# main.net
KiCad netlist of a schematic drawn in Altium Designer
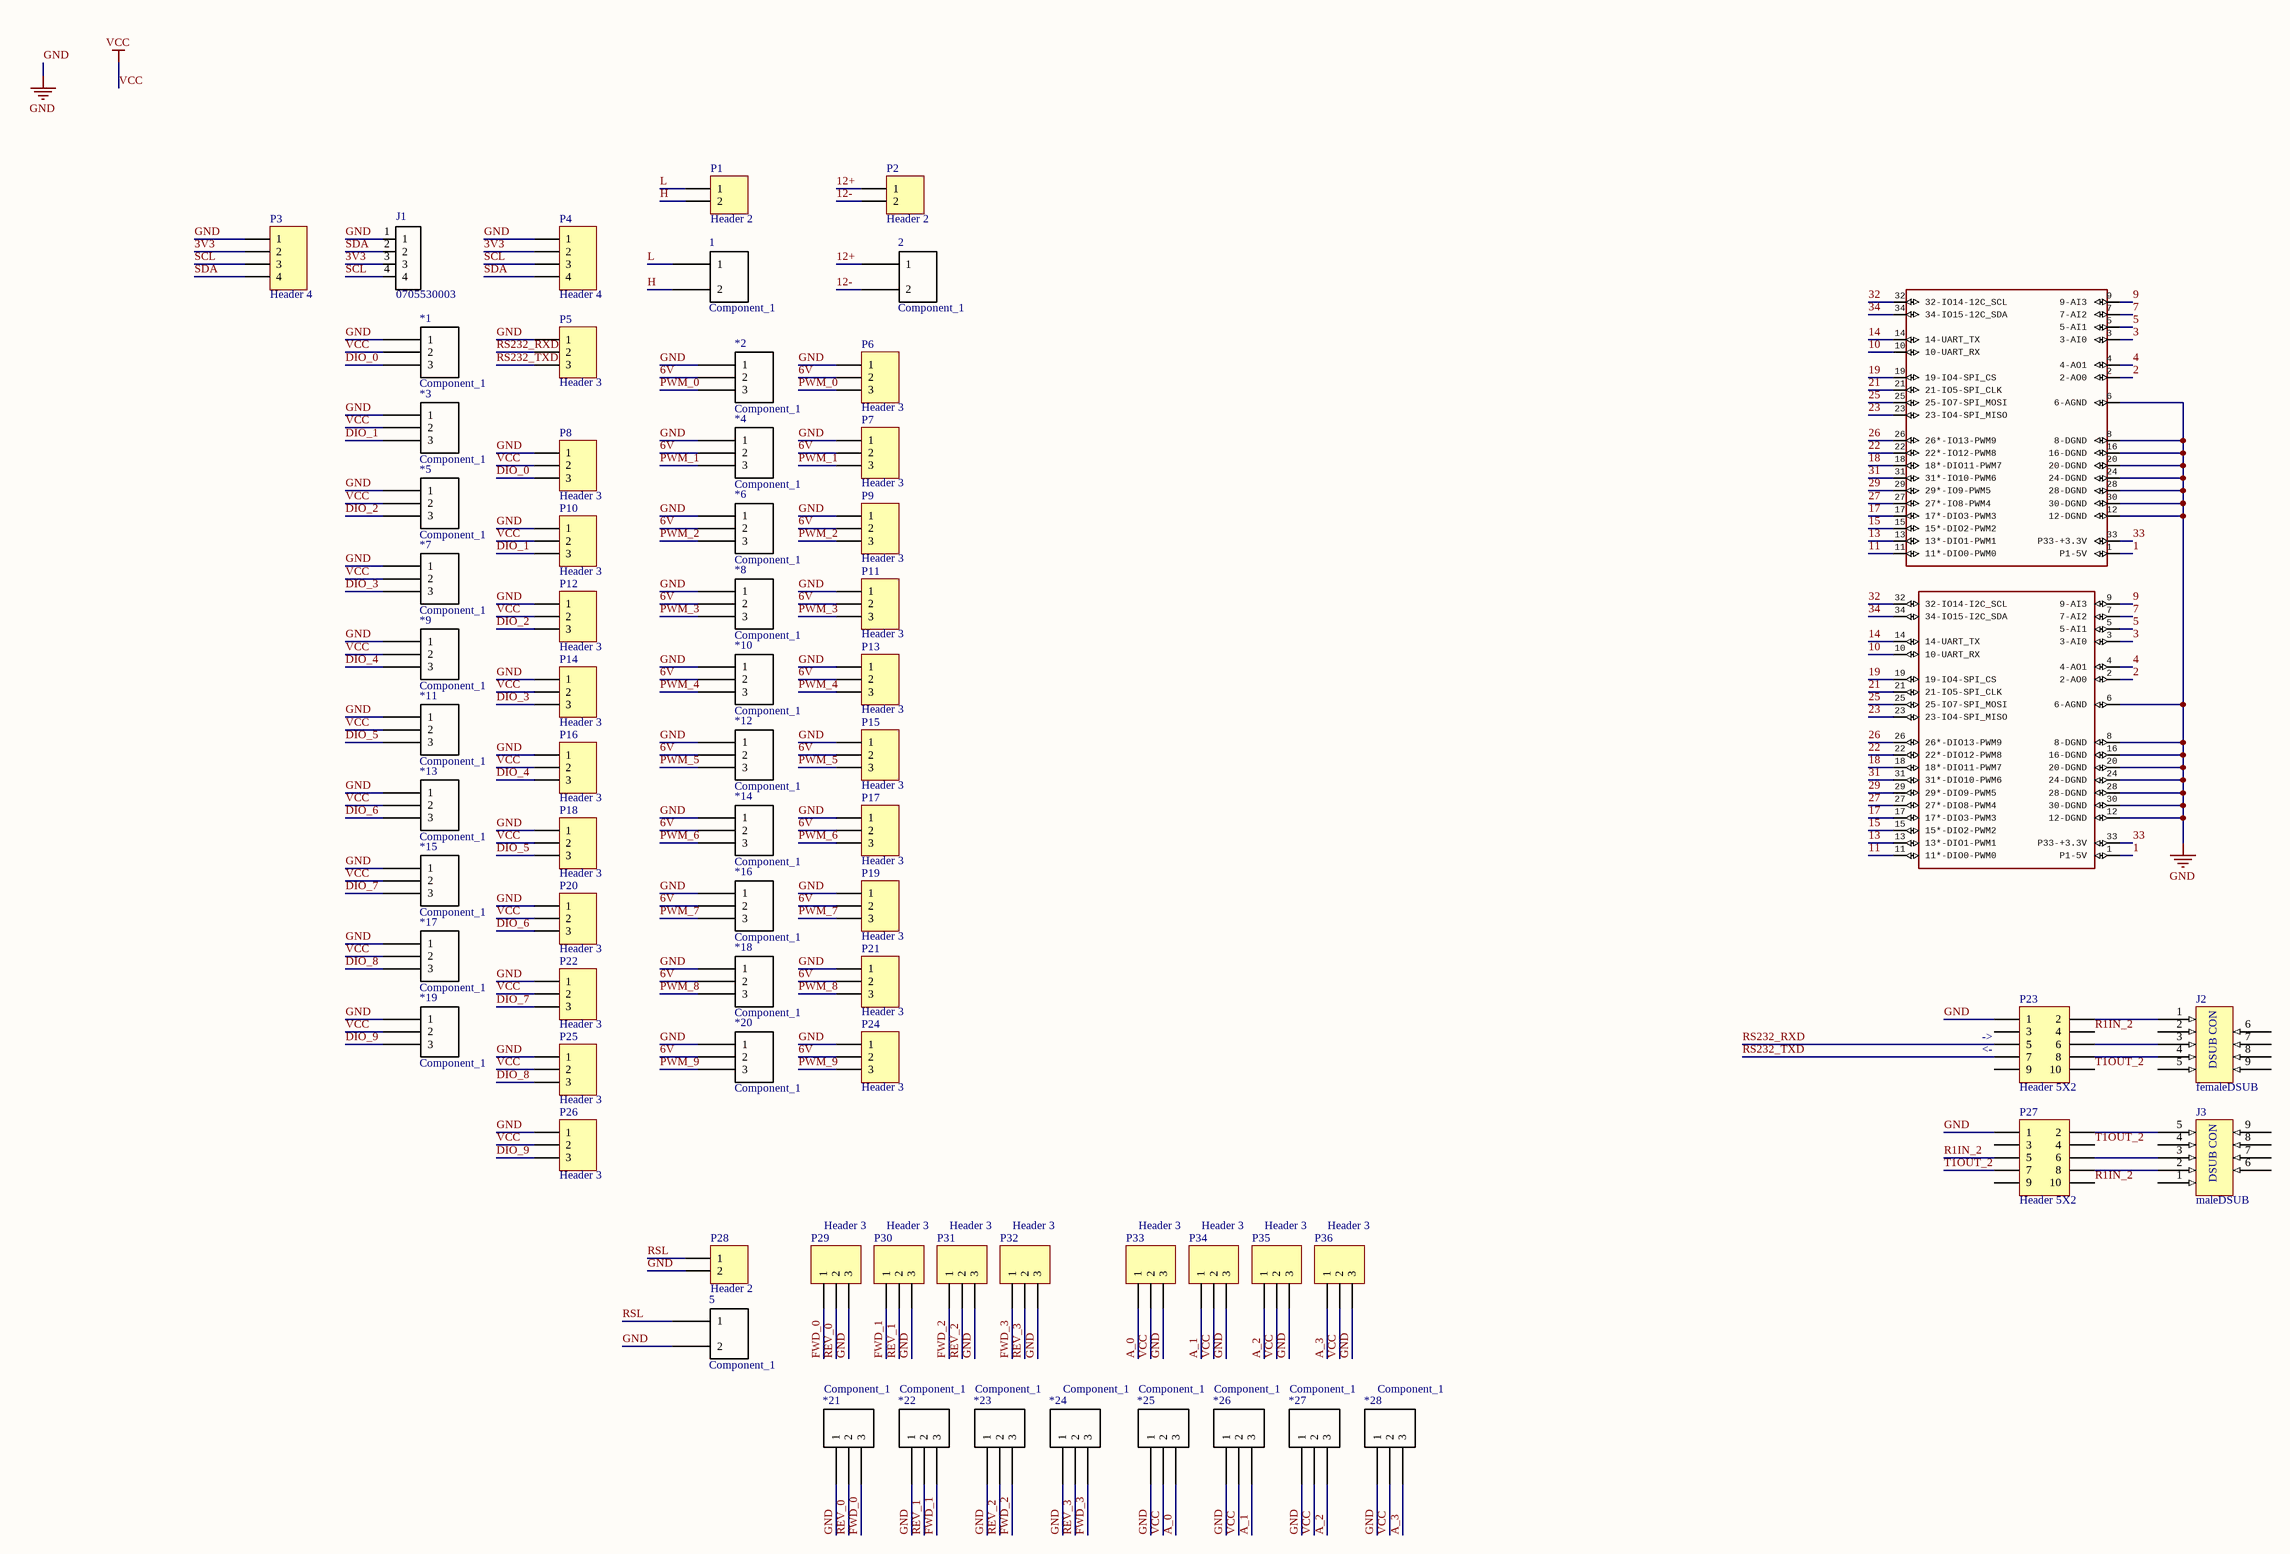
[diagram p0: main.SchDoc]

(export (version "E")
  (design (tool "Eeschema 10.0.6"))
  (components
    (comp (ref "*1")
      (value "Component_1")
      (footprint "3pinmolex")
      (libsource (lib "3 pin") (part "Component_1"))
    )
    (comp (ref "*2")
      (value "Component_1")
      (footprint "3pinmolex")
      (libsource (lib "3 pin") (part "Component_1"))
    )
    (comp (ref "*3")
      (value "Component_1")
      (footprint "3pinmolex")
      (libsource (lib "3 pin") (part "Component_1"))
    )
    (comp (ref "*4")
      (value "Component_1")
      (footprint "3pinmolex")
      (libsource (lib "3 pin") (part "Component_1"))
    )
    (comp (ref "*5")
      (value "Component_1")
      (footprint "3pinmolex")
      (libsource (lib "3 pin") (part "Component_1"))
    )
    (comp (ref "*6")
      (value "Component_1")
      (footprint "3pinmolex")
      (libsource (lib "3 pin") (part "Component_1"))
    )
    (comp (ref "*7")
      (value "Component_1")
      (footprint "3pinmolex")
      (libsource (lib "3 pin") (part "Component_1"))
    )
    (comp (ref "*8")
      (value "Component_1")
      (footprint "3pinmolex")
      (libsource (lib "3 pin") (part "Component_1"))
    )
    (comp (ref "*9")
      (value "Component_1")
      (footprint "3pinmolex")
      (libsource (lib "3 pin") (part "Component_1"))
    )
    (comp (ref "*10")
      (value "Component_1")
      (footprint "3pinmolex")
      (libsource (lib "3 pin") (part "Component_1"))
    )
    (comp (ref "*11")
      (value "Component_1")
      (footprint "3pinmolex")
      (libsource (lib "3 pin") (part "Component_1"))
    )
    (comp (ref "*12")
      (value "Component_1")
      (footprint "3pinmolex")
      (libsource (lib "3 pin") (part "Component_1"))
    )
    (comp (ref "*13")
      (value "Component_1")
      (footprint "3pinmolex")
      (libsource (lib "3 pin") (part "Component_1"))
    )
    (comp (ref "*14")
      (value "Component_1")
      (footprint "3pinmolex")
      (libsource (lib "3 pin") (part "Component_1"))
    )
    (comp (ref "*15")
      (value "Component_1")
      (footprint "3pinmolex")
      (libsource (lib "3 pin") (part "Component_1"))
    )
    (comp (ref "*16")
      (value "Component_1")
      (footprint "3pinmolex")
      (libsource (lib "3 pin") (part "Component_1"))
    )
    (comp (ref "*17")
      (value "Component_1")
      (footprint "3pinmolex")
      (libsource (lib "3 pin") (part "Component_1"))
    )
    (comp (ref "*18")
      (value "Component_1")
      (footprint "3pinmolex")
      (libsource (lib "3 pin") (part "Component_1"))
    )
    (comp (ref "*19")
      (value "Component_1")
      (footprint "3pinmolex")
      (libsource (lib "3 pin") (part "Component_1"))
    )
    (comp (ref "*20")
      (value "Component_1")
      (footprint "3pinmolex")
      (libsource (lib "3 pin") (part "Component_1"))
    )
    (comp (ref "*21")
      (value "Component_1")
      (footprint "3pinmolex")
      (libsource (lib "3 pin") (part "Component_1"))
    )
    (comp (ref "*22")
      (value "Component_1")
      (footprint "3pinmolex")
      (libsource (lib "3 pin") (part "Component_1"))
    )
    (comp (ref "*23")
      (value "Component_1")
      (footprint "3pinmolex")
      (libsource (lib "3 pin") (part "Component_1"))
    )
    (comp (ref "*24")
      (value "Component_1")
      (footprint "3pinmolex")
      (libsource (lib "3 pin") (part "Component_1"))
    )
    (comp (ref "*25")
      (value "Component_1")
      (footprint "3pinmolex")
      (libsource (lib "3 pin") (part "Component_1"))
    )
    (comp (ref "*26")
      (value "Component_1")
      (footprint "3pinmolex")
      (libsource (lib "3 pin") (part "Component_1"))
    )
    (comp (ref "*27")
      (value "Component_1")
      (footprint "3pinmolex")
      (libsource (lib "3 pin") (part "Component_1"))
    )
    (comp (ref "*28")
      (value "Component_1")
      (footprint "3pinmolex")
      (libsource (lib "3 pin") (part "Component_1"))
    )
    (comp (ref "1")
      (value "Component_1")
      (footprint "2pinmolex")
      (libsource (lib "2 pin") (part "Component_1"))
    )
    (comp (ref "2")
      (value "Component_1")
      (footprint "2pinmolex")
      (libsource (lib "2 pin") (part "Component_1"))
    )
    (comp (ref "3")
      (value "RREXTENSION-MALE")
      (footprint "RREXT-MALE")
      (libsource (lib "RoboRioConnector") (part "RREXTENSION-MALE"))
    )
    (comp (ref "4")
      (value "RRINTERFACE-FEMALE")
      (footprint "RRINT-FEMALE")
      (libsource (lib "RoboRioConnector") (part "RRINTERFACE-FEMALE"))
    )
    (comp (ref "5")
      (value "Component_1")
      (footprint "2pinmolex")
      (libsource (lib "2 pin") (part "Component_1"))
    )
    (comp (ref "J1")
      (value "0705530003")
      (footprint "*MOLEX_0705530003")
      (description "Conn Shrouded Header HDR 4 POS 2.54mm Solder RA Thru-Hole SLÃƒÂ¢Ã¢Â€ÂžÂ¢ Tube")
      (fields (field (name "MF") "Molex") (field (name "DIGI-KEY_PART_NUMBER") "WM4902-ND"))
      (libsource (lib "0705530003") (part "0705530003"))
    )
    (comp (ref "J2")
      (value "femaleDSUB")
      (footprint "DSUBfemale")
      (libsource (lib "DSUBconnector") (part "femaleDSUB"))
    )
    (comp (ref "J3")
      (value "maleDSUB")
      (footprint "DSUBmale")
      (libsource (lib "DSUBconnector") (part "maleDSUB"))
    )
    (comp (ref "P1")
      (value "Header 2")
      (footprint "HDR1X2")
      (description "Header, 2-Pin")
      (fields (field (name "PUBLISHER") "Altium Limited"))
      (libsource (lib "Miscellaneous Connectors") (part "Header 2"))
    )
    (comp (ref "P2")
      (value "Header 2")
      (footprint "HDR1X2")
      (description "Header, 2-Pin")
      (fields (field (name "PUBLISHER") "Altium Limited"))
      (libsource (lib "Miscellaneous Connectors") (part "Header 2"))
    )
    (comp (ref "P3")
      (value "Header 4")
      (footprint "HDR1X4")
      (description "Header, 4-Pin")
      (fields (field (name "PUBLISHER") "Altium Limited"))
      (libsource (lib "Miscellaneous Connectors") (part "Header 4"))
    )
    (comp (ref "P4")
      (value "Header 4")
      (footprint "HDR1X4")
      (description "Header, 4-Pin")
      (fields (field (name "PUBLISHER") "Altium Limited"))
      (libsource (lib "Miscellaneous Connectors") (part "Header 4"))
    )
    (comp (ref "P5")
      (value "Header 3")
      (footprint "HDR1X3")
      (description "Header, 3-Pin")
      (fields (field (name "PUBLISHER") "Altium Limited"))
      (libsource (lib "Miscellaneous Connectors") (part "Header 3"))
    )
    (comp (ref "P6")
      (value "Header 3")
      (footprint "HDR1X3")
      (description "Header, 3-Pin")
      (fields (field (name "PUBLISHER") "Altium Limited"))
      (libsource (lib "Miscellaneous Connectors") (part "Header 3"))
    )
    (comp (ref "P7")
      (value "Header 3")
      (footprint "HDR1X3")
      (description "Header, 3-Pin")
      (fields (field (name "PUBLISHER") "Altium Limited"))
      (libsource (lib "Miscellaneous Connectors") (part "Header 3"))
    )
    (comp (ref "P8")
      (value "Header 3")
      (footprint "HDR1X3")
      (description "Header, 3-Pin")
      (fields (field (name "PUBLISHER") "Altium Limited"))
      (libsource (lib "Miscellaneous Connectors") (part "Header 3"))
    )
    (comp (ref "P9")
      (value "Header 3")
      (footprint "HDR1X3")
      (description "Header, 3-Pin")
      (fields (field (name "PUBLISHER") "Altium Limited"))
      (libsource (lib "Miscellaneous Connectors") (part "Header 3"))
    )
    (comp (ref "P10")
      (value "Header 3")
      (footprint "HDR1X3")
      (description "Header, 3-Pin")
      (fields (field (name "PUBLISHER") "Altium Limited"))
      (libsource (lib "Miscellaneous Connectors") (part "Header 3"))
    )
    (comp (ref "P11")
      (value "Header 3")
      (footprint "HDR1X3")
      (description "Header, 3-Pin")
      (fields (field (name "PUBLISHER") "Altium Limited"))
      (libsource (lib "Miscellaneous Connectors") (part "Header 3"))
    )
    (comp (ref "P12")
      (value "Header 3")
      (footprint "HDR1X3")
      (description "Header, 3-Pin")
      (fields (field (name "PUBLISHER") "Altium Limited"))
      (libsource (lib "Miscellaneous Connectors") (part "Header 3"))
    )
    (comp (ref "P13")
      (value "Header 3")
      (footprint "HDR1X3")
      (description "Header, 3-Pin")
      (fields (field (name "PUBLISHER") "Altium Limited"))
      (libsource (lib "Miscellaneous Connectors") (part "Header 3"))
    )
    (comp (ref "P14")
      (value "Header 3")
      (footprint "HDR1X3")
      (description "Header, 3-Pin")
      (fields (field (name "PUBLISHER") "Altium Limited"))
      (libsource (lib "Miscellaneous Connectors") (part "Header 3"))
    )
    (comp (ref "P15")
      (value "Header 3")
      (footprint "HDR1X3")
      (description "Header, 3-Pin")
      (fields (field (name "PUBLISHER") "Altium Limited"))
      (libsource (lib "Miscellaneous Connectors") (part "Header 3"))
    )
    (comp (ref "P16")
      (value "Header 3")
      (footprint "HDR1X3")
      (description "Header, 3-Pin")
      (fields (field (name "PUBLISHER") "Altium Limited"))
      (libsource (lib "Miscellaneous Connectors") (part "Header 3"))
    )
    (comp (ref "P17")
      (value "Header 3")
      (footprint "HDR1X3")
      (description "Header, 3-Pin")
      (fields (field (name "PUBLISHER") "Altium Limited"))
      (libsource (lib "Miscellaneous Connectors") (part "Header 3"))
    )
    (comp (ref "P18")
      (value "Header 3")
      (footprint "HDR1X3")
      (description "Header, 3-Pin")
      (fields (field (name "PUBLISHER") "Altium Limited"))
      (libsource (lib "Miscellaneous Connectors") (part "Header 3"))
    )
    (comp (ref "P19")
      (value "Header 3")
      (footprint "HDR1X3")
      (description "Header, 3-Pin")
      (fields (field (name "PUBLISHER") "Altium Limited"))
      (libsource (lib "Miscellaneous Connectors") (part "Header 3"))
    )
    (comp (ref "P20")
      (value "Header 3")
      (footprint "HDR1X3")
      (description "Header, 3-Pin")
      (fields (field (name "PUBLISHER") "Altium Limited"))
      (libsource (lib "Miscellaneous Connectors") (part "Header 3"))
    )
    (comp (ref "P21")
      (value "Header 3")
      (footprint "HDR1X3")
      (description "Header, 3-Pin")
      (fields (field (name "PUBLISHER") "Altium Limited"))
      (libsource (lib "Miscellaneous Connectors") (part "Header 3"))
    )
    (comp (ref "P22")
      (value "Header 3")
      (footprint "HDR1X3")
      (description "Header, 3-Pin")
      (fields (field (name "PUBLISHER") "Altium Limited"))
      (libsource (lib "Miscellaneous Connectors") (part "Header 3"))
    )
    (comp (ref "P23")
      (value "Header 5X2")
      (footprint "HDR2X5")
      (description "Header, 5-Pin, Dual row")
      (fields (field (name "PUBLISHER") "Altium Limited"))
      (libsource (lib "Miscellaneous Connectors") (part "Header 5X2"))
    )
    (comp (ref "P24")
      (value "Header 3")
      (footprint "HDR1X3")
      (description "Header, 3-Pin")
      (fields (field (name "PUBLISHER") "Altium Limited"))
      (libsource (lib "Miscellaneous Connectors") (part "Header 3"))
    )
    (comp (ref "P25")
      (value "Header 3")
      (footprint "HDR1X3")
      (description "Header, 3-Pin")
      (fields (field (name "PUBLISHER") "Altium Limited"))
      (libsource (lib "Miscellaneous Connectors") (part "Header 3"))
    )
    (comp (ref "P26")
      (value "Header 3")
      (footprint "HDR1X3")
      (description "Header, 3-Pin")
      (fields (field (name "PUBLISHER") "Altium Limited"))
      (libsource (lib "Miscellaneous Connectors") (part "Header 3"))
    )
    (comp (ref "P27")
      (value "Header 5X2")
      (footprint "HDR2X5")
      (description "Header, 5-Pin, Dual row")
      (fields (field (name "PUBLISHER") "Altium Limited"))
      (libsource (lib "Miscellaneous Connectors") (part "Header 5X2"))
    )
    (comp (ref "P28")
      (value "Header 2")
      (footprint "HDR1X2")
      (description "Header, 2-Pin")
      (fields (field (name "PUBLISHER") "Altium Limited"))
      (libsource (lib "Miscellaneous Connectors") (part "Header 2"))
    )
    (comp (ref "P29")
      (value "Header 3")
      (footprint "HDR1X3")
      (description "Header, 3-Pin")
      (fields (field (name "PUBLISHER") "Altium Limited"))
      (libsource (lib "") (part "Header 3_1"))
    )
    (comp (ref "P30")
      (value "Header 3")
      (footprint "HDR1X3")
      (description "Header, 3-Pin")
      (fields (field (name "PUBLISHER") "Altium Limited"))
      (libsource (lib "") (part "Header 3_1"))
    )
    (comp (ref "P31")
      (value "Header 3")
      (footprint "HDR1X3")
      (description "Header, 3-Pin")
      (fields (field (name "PUBLISHER") "Altium Limited"))
      (libsource (lib "") (part "Header 3_1"))
    )
    (comp (ref "P32")
      (value "Header 3")
      (footprint "HDR1X3")
      (description "Header, 3-Pin")
      (fields (field (name "PUBLISHER") "Altium Limited"))
      (libsource (lib "") (part "Header 3_1"))
    )
    (comp (ref "P33")
      (value "Header 3")
      (footprint "HDR1X3")
      (description "Header, 3-Pin")
      (fields (field (name "PUBLISHER") "Altium Limited"))
      (libsource (lib "") (part "Header 3_1"))
    )
    (comp (ref "P34")
      (value "Header 3")
      (footprint "HDR1X3")
      (description "Header, 3-Pin")
      (fields (field (name "PUBLISHER") "Altium Limited"))
      (libsource (lib "") (part "Header 3_1"))
    )
    (comp (ref "P35")
      (value "Header 3")
      (footprint "HDR1X3")
      (description "Header, 3-Pin")
      (fields (field (name "PUBLISHER") "Altium Limited"))
      (libsource (lib "") (part "Header 3_1"))
    )
    (comp (ref "P36")
      (value "Header 3")
      (footprint "HDR1X3")
      (description "Header, 3-Pin")
      (fields (field (name "PUBLISHER") "Altium Limited"))
      (libsource (lib "") (part "Header 3_1"))
    )
  )
  (nets
    (net (code "1") (name "/1") (class "Default")
      (node (ref "3") (pin "1") (pinfunction "P1-5V_1") (pintype "bidirectional"))
      (node (ref "4") (pin "1") (pinfunction "P1-5V_1") (pintype "bidirectional"))
    )
    (net (code "2") (name "/2") (class "Default")
      (node (ref "3") (pin "2") (pinfunction "2-AO0_2") (pintype "bidirectional"))
      (node (ref "4") (pin "2") (pinfunction "2-AO0_2") (pintype "bidirectional"))
    )
    (net (code "3") (name "/3") (class "Default")
      (node (ref "3") (pin "3") (pinfunction "3-AI0_3") (pintype "bidirectional"))
      (node (ref "4") (pin "3") (pinfunction "3-AI0_3") (pintype "bidirectional"))
    )
    (net (code "4") (name "/3V3") (class "Default")
      (node (ref "J1") (pin "3") (pinfunction "3_3") (pintype "passive"))
      (node (ref "P3") (pin "2") (pinfunction "2_2") (pintype "passive"))
      (node (ref "P4") (pin "2") (pinfunction "2_2") (pintype "passive"))
    )
    (net (code "5") (name "/4") (class "Default")
      (node (ref "3") (pin "4") (pinfunction "4-AO1_4") (pintype "bidirectional"))
      (node (ref "4") (pin "4") (pinfunction "4-AO1_4") (pintype "bidirectional"))
    )
    (net (code "6") (name "/5") (class "Default")
      (node (ref "3") (pin "5") (pinfunction "5-AI1_5") (pintype "bidirectional"))
      (node (ref "4") (pin "5") (pinfunction "5-AI1_5") (pintype "bidirectional"))
    )
    (net (code "7") (name "/6V") (class "Default")
      (node (ref "*10") (pin "2") (pinfunction "2_2") (pintype "passive"))
      (node (ref "*12") (pin "2") (pinfunction "2_2") (pintype "passive"))
      (node (ref "*14") (pin "2") (pinfunction "2_2") (pintype "passive"))
      (node (ref "*16") (pin "2") (pinfunction "2_2") (pintype "passive"))
      (node (ref "*18") (pin "2") (pinfunction "2_2") (pintype "passive"))
      (node (ref "*2") (pin "2") (pinfunction "2_2") (pintype "passive"))
      (node (ref "*20") (pin "2") (pinfunction "2_2") (pintype "passive"))
      (node (ref "*4") (pin "2") (pinfunction "2_2") (pintype "passive"))
      (node (ref "*6") (pin "2") (pinfunction "2_2") (pintype "passive"))
      (node (ref "*8") (pin "2") (pinfunction "2_2") (pintype "passive"))
      (node (ref "P11") (pin "2") (pinfunction "2_2") (pintype "passive"))
      (node (ref "P13") (pin "2") (pinfunction "2_2") (pintype "passive"))
      (node (ref "P15") (pin "2") (pinfunction "2_2") (pintype "passive"))
      (node (ref "P17") (pin "2") (pinfunction "2_2") (pintype "passive"))
      (node (ref "P19") (pin "2") (pinfunction "2_2") (pintype "passive"))
      (node (ref "P21") (pin "2") (pinfunction "2_2") (pintype "passive"))
      (node (ref "P24") (pin "2") (pinfunction "2_2") (pintype "passive"))
      (node (ref "P6") (pin "2") (pinfunction "2_2") (pintype "passive"))
      (node (ref "P7") (pin "2") (pinfunction "2_2") (pintype "passive"))
      (node (ref "P9") (pin "2") (pinfunction "2_2") (pintype "passive"))
    )
    (net (code "8") (name "/7") (class "Default")
      (node (ref "3") (pin "7") (pinfunction "7-AI2_7") (pintype "bidirectional"))
      (node (ref "4") (pin "7") (pinfunction "7-AI2_7") (pintype "bidirectional"))
    )
    (net (code "9") (name "/9") (class "Default")
      (node (ref "3") (pin "9") (pinfunction "9-AI3_9") (pintype "bidirectional"))
      (node (ref "4") (pin "9") (pinfunction "9-AI3_9") (pintype "bidirectional"))
    )
    (net (code "10") (name "/10") (class "Default")
      (node (ref "3") (pin "10") (pinfunction "10-UART_RX_10") (pintype "bidirectional"))
      (node (ref "4") (pin "10") (pinfunction "10-UART_RX_10") (pintype "bidirectional"))
    )
    (net (code "11") (name "/11") (class "Default")
      (node (ref "3") (pin "11") (pinfunction "11*-DIO0-PWM0_11") (pintype "bidirectional"))
      (node (ref "4") (pin "11") (pinfunction "11*-DIO0-PWM0_11") (pintype "bidirectional"))
    )
    (net (code "12") (name "/12+") (class "Default")
      (node (ref "2") (pin "1") (pinfunction "1_1") (pintype "passive"))
      (node (ref "P2") (pin "1") (pinfunction "1_1") (pintype "passive"))
    )
    (net (code "13") (name "/12-") (class "Default")
      (node (ref "2") (pin "2") (pinfunction "2_2") (pintype "passive"))
      (node (ref "P2") (pin "2") (pinfunction "2_2") (pintype "passive"))
    )
    (net (code "14") (name "/13") (class "Default")
      (node (ref "3") (pin "13") (pinfunction "13*-DIO1-PWM1_13") (pintype "bidirectional"))
      (node (ref "4") (pin "13") (pinfunction "13*-DIO1-PWM1_13") (pintype "bidirectional"))
    )
    (net (code "15") (name "/14") (class "Default")
      (node (ref "3") (pin "14") (pinfunction "14-UART_TX_14") (pintype "bidirectional"))
      (node (ref "4") (pin "14") (pinfunction "14-UART_TX_14") (pintype "bidirectional"))
    )
    (net (code "16") (name "/15") (class "Default")
      (node (ref "3") (pin "15") (pinfunction "15*-DIO2-PWM2_15") (pintype "bidirectional"))
      (node (ref "4") (pin "15") (pinfunction "15*-DIO2-PWM2_15") (pintype "bidirectional"))
    )
    (net (code "17") (name "/17") (class "Default")
      (node (ref "3") (pin "17") (pinfunction "17*-DIO3-PWM3_17") (pintype "bidirectional"))
      (node (ref "4") (pin "17") (pinfunction "17*-DIO3-PWM3_17") (pintype "bidirectional"))
    )
    (net (code "18") (name "/18") (class "Default")
      (node (ref "3") (pin "18") (pinfunction "18*-DIO11-PWM7_18") (pintype "bidirectional"))
      (node (ref "4") (pin "18") (pinfunction "18*-DIO11-PWM7_18") (pintype "bidirectional"))
    )
    (net (code "19") (name "/19") (class "Default")
      (node (ref "3") (pin "19") (pinfunction "19-IO4-SPI_CS_19") (pintype "bidirectional"))
      (node (ref "4") (pin "19") (pinfunction "19-IO4-SPI_CS_19") (pintype "bidirectional"))
    )
    (net (code "20") (name "/21") (class "Default")
      (node (ref "3") (pin "21") (pinfunction "21-IO5-SPI_CLK_21") (pintype "bidirectional"))
      (node (ref "4") (pin "21") (pinfunction "21-IO5-SPI_CLK_21") (pintype "bidirectional"))
    )
    (net (code "21") (name "/22") (class "Default")
      (node (ref "3") (pin "22") (pinfunction "22*-IO12-PWM8_22") (pintype "bidirectional"))
      (node (ref "4") (pin "22") (pinfunction "22*-DIO12-PWM8_22") (pintype "bidirectional"))
    )
    (net (code "22") (name "/23") (class "Default")
      (node (ref "3") (pin "23") (pinfunction "23-IO4-SPI_MISO_23") (pintype "bidirectional"))
      (node (ref "4") (pin "23") (pinfunction "23-IO4-SPI_MISO_23") (pintype "bidirectional"))
    )
    (net (code "23") (name "/25") (class "Default")
      (node (ref "3") (pin "25") (pinfunction "25-IO7-SPI_MOSI_25") (pintype "bidirectional"))
      (node (ref "4") (pin "25") (pinfunction "25-IO7-SPI_MOSI_25") (pintype "bidirectional"))
    )
    (net (code "24") (name "/26") (class "Default")
      (node (ref "3") (pin "26") (pinfunction "26*-IO13-PWM9_26") (pintype "bidirectional"))
      (node (ref "4") (pin "26") (pinfunction "26*-DIO13-PWM9_26") (pintype "bidirectional"))
    )
    (net (code "25") (name "/27") (class "Default")
      (node (ref "3") (pin "27") (pinfunction "27*-IO8-PWM4_27") (pintype "bidirectional"))
      (node (ref "4") (pin "27") (pinfunction "27*-DIO8-PWM4_27") (pintype "bidirectional"))
    )
    (net (code "26") (name "/29") (class "Default")
      (node (ref "3") (pin "29") (pinfunction "29*-IO9-PWM5_29") (pintype "bidirectional"))
      (node (ref "4") (pin "29") (pinfunction "29*-DIO9-PWM5_29") (pintype "bidirectional"))
    )
    (net (code "27") (name "/31") (class "Default")
      (node (ref "3") (pin "31") (pinfunction "31*-IO10-PWM6_31") (pintype "bidirectional"))
      (node (ref "4") (pin "31") (pinfunction "31*-DIO10-PWM6_31") (pintype "bidirectional"))
    )
    (net (code "28") (name "/32") (class "Default")
      (node (ref "3") (pin "32") (pinfunction "32-IO14-12C_SCL_32") (pintype "bidirectional"))
      (node (ref "4") (pin "32") (pinfunction "32-IO14-I2C_SCL_32") (pintype "bidirectional"))
    )
    (net (code "29") (name "/33") (class "Default")
      (node (ref "3") (pin "33") (pinfunction "P33-+3.3V_33") (pintype "bidirectional"))
      (node (ref "4") (pin "33") (pinfunction "P33-+3.3V_33") (pintype "bidirectional"))
    )
    (net (code "30") (name "/34") (class "Default")
      (node (ref "3") (pin "34") (pinfunction "34-IO15-12C_SDA_34") (pintype "bidirectional"))
      (node (ref "4") (pin "34") (pinfunction "34-IO15-I2C_SDA_34") (pintype "bidirectional"))
    )
    (net (code "31") (name "/A_0") (class "Default")
      (node (ref "*25") (pin "3") (pinfunction "3_3") (pintype "passive"))
      (node (ref "P33") (pin "1") (pinfunction "1_1") (pintype "passive"))
    )
    (net (code "32") (name "/A_1") (class "Default")
      (node (ref "*26") (pin "3") (pinfunction "3_3") (pintype "passive"))
      (node (ref "P34") (pin "1") (pinfunction "1_1") (pintype "passive"))
    )
    (net (code "33") (name "/A_2") (class "Default")
      (node (ref "*27") (pin "3") (pinfunction "3_3") (pintype "passive"))
      (node (ref "P35") (pin "1") (pinfunction "1_1") (pintype "passive"))
    )
    (net (code "34") (name "/A_3") (class "Default")
      (node (ref "*28") (pin "3") (pinfunction "3_3") (pintype "passive"))
      (node (ref "P36") (pin "1") (pinfunction "1_1") (pintype "passive"))
    )
    (net (code "35") (name "/DIO_0") (class "Default")
      (node (ref "*1") (pin "3") (pinfunction "3_3") (pintype "passive"))
      (node (ref "P8") (pin "3") (pinfunction "3_3") (pintype "passive"))
    )
    (net (code "36") (name "/DIO_1") (class "Default")
      (node (ref "*3") (pin "3") (pinfunction "3_3") (pintype "passive"))
      (node (ref "P10") (pin "3") (pinfunction "3_3") (pintype "passive"))
    )
    (net (code "37") (name "/DIO_2") (class "Default")
      (node (ref "*5") (pin "3") (pinfunction "3_3") (pintype "passive"))
      (node (ref "P12") (pin "3") (pinfunction "3_3") (pintype "passive"))
    )
    (net (code "38") (name "/DIO_3") (class "Default")
      (node (ref "*7") (pin "3") (pinfunction "3_3") (pintype "passive"))
      (node (ref "P14") (pin "3") (pinfunction "3_3") (pintype "passive"))
    )
    (net (code "39") (name "/DIO_4") (class "Default")
      (node (ref "*9") (pin "3") (pinfunction "3_3") (pintype "passive"))
      (node (ref "P16") (pin "3") (pinfunction "3_3") (pintype "passive"))
    )
    (net (code "40") (name "/DIO_5") (class "Default")
      (node (ref "*11") (pin "3") (pinfunction "3_3") (pintype "passive"))
      (node (ref "P18") (pin "3") (pinfunction "3_3") (pintype "passive"))
    )
    (net (code "41") (name "/DIO_6") (class "Default")
      (node (ref "*13") (pin "3") (pinfunction "3_3") (pintype "passive"))
      (node (ref "P20") (pin "3") (pinfunction "3_3") (pintype "passive"))
    )
    (net (code "42") (name "/DIO_7") (class "Default")
      (node (ref "*15") (pin "3") (pinfunction "3_3") (pintype "passive"))
      (node (ref "P22") (pin "3") (pinfunction "3_3") (pintype "passive"))
    )
    (net (code "43") (name "/DIO_8") (class "Default")
      (node (ref "*17") (pin "3") (pinfunction "3_3") (pintype "passive"))
      (node (ref "P25") (pin "3") (pinfunction "3_3") (pintype "passive"))
    )
    (net (code "44") (name "/DIO_9") (class "Default")
      (node (ref "*19") (pin "3") (pinfunction "3_3") (pintype "passive"))
      (node (ref "P26") (pin "3") (pinfunction "3_3") (pintype "passive"))
    )
    (net (code "45") (name "/FWD_0") (class "Default")
      (node (ref "*21") (pin "3") (pinfunction "3_3") (pintype "passive"))
      (node (ref "P29") (pin "1") (pinfunction "1_1") (pintype "passive"))
    )
    (net (code "46") (name "/FWD_1") (class "Default")
      (node (ref "*22") (pin "3") (pinfunction "3_3") (pintype "passive"))
      (node (ref "P30") (pin "1") (pinfunction "1_1") (pintype "passive"))
    )
    (net (code "47") (name "/FWD_2") (class "Default")
      (node (ref "*23") (pin "3") (pinfunction "3_3") (pintype "passive"))
      (node (ref "P31") (pin "1") (pinfunction "1_1") (pintype "passive"))
    )
    (net (code "48") (name "/FWD_3") (class "Default")
      (node (ref "*24") (pin "3") (pinfunction "3_3") (pintype "passive"))
      (node (ref "P32") (pin "1") (pinfunction "1_1") (pintype "passive"))
    )
    (net (code "49") (name "/H") (class "Default")
      (node (ref "1") (pin "2") (pinfunction "2_2") (pintype "passive"))
      (node (ref "P1") (pin "2") (pinfunction "2_2") (pintype "passive"))
    )
    (net (code "50") (name "/L") (class "Default")
      (node (ref "1") (pin "1") (pinfunction "1_1") (pintype "passive"))
      (node (ref "P1") (pin "1") (pinfunction "1_1") (pintype "passive"))
    )
    (net (code "51") (name "/PWM_0") (class "Default")
      (node (ref "*2") (pin "3") (pinfunction "3_3") (pintype "passive"))
      (node (ref "P6") (pin "3") (pinfunction "3_3") (pintype "passive"))
    )
    (net (code "52") (name "/PWM_1") (class "Default")
      (node (ref "*4") (pin "3") (pinfunction "3_3") (pintype "passive"))
      (node (ref "P7") (pin "3") (pinfunction "3_3") (pintype "passive"))
    )
    (net (code "53") (name "/PWM_2") (class "Default")
      (node (ref "*6") (pin "3") (pinfunction "3_3") (pintype "passive"))
      (node (ref "P9") (pin "3") (pinfunction "3_3") (pintype "passive"))
    )
    (net (code "54") (name "/PWM_3") (class "Default")
      (node (ref "*8") (pin "3") (pinfunction "3_3") (pintype "passive"))
      (node (ref "P11") (pin "3") (pinfunction "3_3") (pintype "passive"))
    )
    (net (code "55") (name "/PWM_4") (class "Default")
      (node (ref "*10") (pin "3") (pinfunction "3_3") (pintype "passive"))
      (node (ref "P13") (pin "3") (pinfunction "3_3") (pintype "passive"))
    )
    (net (code "56") (name "/PWM_5") (class "Default")
      (node (ref "*12") (pin "3") (pinfunction "3_3") (pintype "passive"))
      (node (ref "P15") (pin "3") (pinfunction "3_3") (pintype "passive"))
    )
    (net (code "57") (name "/PWM_6") (class "Default")
      (node (ref "*14") (pin "3") (pinfunction "3_3") (pintype "passive"))
      (node (ref "P17") (pin "3") (pinfunction "3_3") (pintype "passive"))
    )
    (net (code "58") (name "/PWM_7") (class "Default")
      (node (ref "*16") (pin "3") (pinfunction "3_3") (pintype "passive"))
      (node (ref "P19") (pin "3") (pinfunction "3_3") (pintype "passive"))
    )
    (net (code "59") (name "/PWM_8") (class "Default")
      (node (ref "*18") (pin "3") (pinfunction "3_3") (pintype "passive"))
      (node (ref "P21") (pin "3") (pinfunction "3_3") (pintype "passive"))
    )
    (net (code "60") (name "/PWM_9") (class "Default")
      (node (ref "*20") (pin "3") (pinfunction "3_3") (pintype "passive"))
      (node (ref "P24") (pin "3") (pinfunction "3_3") (pintype "passive"))
    )
    (net (code "61") (name "/R1IN_2") (class "Default")
      (node (ref "P23") (pin "4") (pinfunction "4_4") (pintype "passive"))
      (node (ref "P27") (pin "10") (pinfunction "10_10") (pintype "passive"))
      (node (ref "P27") (pin "5") (pinfunction "5_5") (pintype "passive"))
    )
    (net (code "62") (name "/REV_0") (class "Default")
      (node (ref "*21") (pin "2") (pinfunction "2_2") (pintype "passive"))
      (node (ref "P29") (pin "2") (pinfunction "2_2") (pintype "passive"))
    )
    (net (code "63") (name "/REV_1") (class "Default")
      (node (ref "*22") (pin "2") (pinfunction "2_2") (pintype "passive"))
      (node (ref "P30") (pin "2") (pinfunction "2_2") (pintype "passive"))
    )
    (net (code "64") (name "/REV_2") (class "Default")
      (node (ref "*23") (pin "2") (pinfunction "2_2") (pintype "passive"))
      (node (ref "P31") (pin "2") (pinfunction "2_2") (pintype "passive"))
    )
    (net (code "65") (name "/REV_3") (class "Default")
      (node (ref "*24") (pin "2") (pinfunction "2_2") (pintype "passive"))
      (node (ref "P32") (pin "2") (pinfunction "2_2") (pintype "passive"))
    )
    (net (code "66") (name "/RS232_RXD") (class "Default")
      (node (ref "P23") (pin "5") (pinfunction "5_5") (pintype "passive"))
      (node (ref "P5") (pin "2") (pinfunction "2_2") (pintype "passive"))
    )
    (net (code "67") (name "/RS232_TXD") (class "Default")
      (node (ref "P23") (pin "7") (pinfunction "7_7") (pintype "passive"))
      (node (ref "P5") (pin "3") (pinfunction "3_3") (pintype "passive"))
    )
    (net (code "68") (name "/RSL") (class "Default")
      (node (ref "5") (pin "1") (pinfunction "1_1") (pintype "passive"))
      (node (ref "P28") (pin "1") (pinfunction "1_1") (pintype "passive"))
    )
    (net (code "69") (name "/SCL") (class "Default")
      (node (ref "J1") (pin "4") (pinfunction "4_4") (pintype "passive"))
      (node (ref "P3") (pin "3") (pinfunction "3_3") (pintype "passive"))
      (node (ref "P4") (pin "3") (pinfunction "3_3") (pintype "passive"))
    )
    (net (code "70") (name "/SDA") (class "Default")
      (node (ref "J1") (pin "2") (pinfunction "2_2") (pintype "passive"))
      (node (ref "P3") (pin "4") (pinfunction "4_4") (pintype "passive"))
      (node (ref "P4") (pin "4") (pinfunction "4_4") (pintype "passive"))
    )
    (net (code "71") (name "/T1OUT_2") (class "Default")
      (node (ref "P23") (pin "10") (pinfunction "10_10") (pintype "passive"))
      (node (ref "P27") (pin "4") (pinfunction "4_4") (pintype "passive"))
      (node (ref "P27") (pin "7") (pinfunction "7_7") (pintype "passive"))
    )
    (net (code "72") (name "GND") (class "Default")
      (node (ref "*1") (pin "1") (pinfunction "1_1") (pintype "passive"))
      (node (ref "*10") (pin "1") (pinfunction "1_1") (pintype "passive"))
      (node (ref "*11") (pin "1") (pinfunction "1_1") (pintype "passive"))
      (node (ref "*12") (pin "1") (pinfunction "1_1") (pintype "passive"))
      (node (ref "*13") (pin "1") (pinfunction "1_1") (pintype "passive"))
      (node (ref "*14") (pin "1") (pinfunction "1_1") (pintype "passive"))
      (node (ref "*15") (pin "1") (pinfunction "1_1") (pintype "passive"))
      (node (ref "*16") (pin "1") (pinfunction "1_1") (pintype "passive"))
      (node (ref "*17") (pin "1") (pinfunction "1_1") (pintype "passive"))
      (node (ref "*18") (pin "1") (pinfunction "1_1") (pintype "passive"))
      (node (ref "*19") (pin "1") (pinfunction "1_1") (pintype "passive"))
      (node (ref "*2") (pin "1") (pinfunction "1_1") (pintype "passive"))
      (node (ref "*20") (pin "1") (pinfunction "1_1") (pintype "passive"))
      (node (ref "*21") (pin "1") (pinfunction "1_1") (pintype "passive"))
      (node (ref "*22") (pin "1") (pinfunction "1_1") (pintype "passive"))
      (node (ref "*23") (pin "1") (pinfunction "1_1") (pintype "passive"))
      (node (ref "*24") (pin "1") (pinfunction "1_1") (pintype "passive"))
      (node (ref "*25") (pin "1") (pinfunction "1_1") (pintype "passive"))
      (node (ref "*26") (pin "1") (pinfunction "1_1") (pintype "passive"))
      (node (ref "*27") (pin "1") (pinfunction "1_1") (pintype "passive"))
      (node (ref "*28") (pin "1") (pinfunction "1_1") (pintype "passive"))
      (node (ref "*3") (pin "1") (pinfunction "1_1") (pintype "passive"))
      (node (ref "*4") (pin "1") (pinfunction "1_1") (pintype "passive"))
      (node (ref "*5") (pin "1") (pinfunction "1_1") (pintype "passive"))
      (node (ref "*6") (pin "1") (pinfunction "1_1") (pintype "passive"))
      (node (ref "*7") (pin "1") (pinfunction "1_1") (pintype "passive"))
      (node (ref "*8") (pin "1") (pinfunction "1_1") (pintype "passive"))
      (node (ref "*9") (pin "1") (pinfunction "1_1") (pintype "passive"))
      (node (ref "3") (pin "12") (pinfunction "12-DGND_12") (pintype "bidirectional"))
      (node (ref "3") (pin "16") (pinfunction "16-DGND_16") (pintype "bidirectional"))
      (node (ref "3") (pin "20") (pinfunction "20-DGND_20") (pintype "bidirectional"))
      (node (ref "3") (pin "24") (pinfunction "24-DGND_24") (pintype "bidirectional"))
      (node (ref "3") (pin "28") (pinfunction "28-DGND_28") (pintype "bidirectional"))
      (node (ref "3") (pin "30") (pinfunction "30-DGND_30") (pintype "bidirectional"))
      (node (ref "3") (pin "6") (pinfunction "6-AGND_6") (pintype "bidirectional"))
      (node (ref "3") (pin "8") (pinfunction "8-DGND_8") (pintype "bidirectional"))
      (node (ref "4") (pin "12") (pinfunction "12-DGND_12") (pintype "bidirectional"))
      (node (ref "4") (pin "16") (pinfunction "16-DGND_16") (pintype "bidirectional"))
      (node (ref "4") (pin "20") (pinfunction "20-DGND_20") (pintype "bidirectional"))
      (node (ref "4") (pin "24") (pinfunction "24-DGND_24") (pintype "bidirectional"))
      (node (ref "4") (pin "28") (pinfunction "28-DGND_28") (pintype "bidirectional"))
      (node (ref "4") (pin "30") (pinfunction "30-DGND_30") (pintype "bidirectional"))
      (node (ref "4") (pin "6") (pinfunction "6-AGND_6") (pintype "bidirectional"))
      (node (ref "4") (pin "8") (pinfunction "8-DGND_8") (pintype "bidirectional"))
      (node (ref "5") (pin "2") (pinfunction "2_2") (pintype "passive"))
      (node (ref "J1") (pin "1") (pinfunction "1_1") (pintype "passive"))
      (node (ref "P10") (pin "1") (pinfunction "1_1") (pintype "passive"))
      (node (ref "P11") (pin "1") (pinfunction "1_1") (pintype "passive"))
      (node (ref "P12") (pin "1") (pinfunction "1_1") (pintype "passive"))
      (node (ref "P13") (pin "1") (pinfunction "1_1") (pintype "passive"))
      (node (ref "P14") (pin "1") (pinfunction "1_1") (pintype "passive"))
      (node (ref "P15") (pin "1") (pinfunction "1_1") (pintype "passive"))
      (node (ref "P16") (pin "1") (pinfunction "1_1") (pintype "passive"))
      (node (ref "P17") (pin "1") (pinfunction "1_1") (pintype "passive"))
      (node (ref "P18") (pin "1") (pinfunction "1_1") (pintype "passive"))
      (node (ref "P19") (pin "1") (pinfunction "1_1") (pintype "passive"))
      (node (ref "P20") (pin "1") (pinfunction "1_1") (pintype "passive"))
      (node (ref "P21") (pin "1") (pinfunction "1_1") (pintype "passive"))
      (node (ref "P22") (pin "1") (pinfunction "1_1") (pintype "passive"))
      (node (ref "P23") (pin "1") (pinfunction "1_1") (pintype "passive"))
      (node (ref "P24") (pin "1") (pinfunction "1_1") (pintype "passive"))
      (node (ref "P25") (pin "1") (pinfunction "1_1") (pintype "passive"))
      (node (ref "P26") (pin "1") (pinfunction "1_1") (pintype "passive"))
      (node (ref "P27") (pin "1") (pinfunction "1_1") (pintype "passive"))
      (node (ref "P28") (pin "2") (pinfunction "2_2") (pintype "passive"))
      (node (ref "P29") (pin "3") (pinfunction "3_3") (pintype "passive"))
      (node (ref "P3") (pin "1") (pinfunction "1_1") (pintype "passive"))
      (node (ref "P30") (pin "3") (pinfunction "3_3") (pintype "passive"))
      (node (ref "P31") (pin "3") (pinfunction "3_3") (pintype "passive"))
      (node (ref "P32") (pin "3") (pinfunction "3_3") (pintype "passive"))
      (node (ref "P33") (pin "3") (pinfunction "3_3") (pintype "passive"))
      (node (ref "P34") (pin "3") (pinfunction "3_3") (pintype "passive"))
      (node (ref "P35") (pin "3") (pinfunction "3_3") (pintype "passive"))
      (node (ref "P36") (pin "3") (pinfunction "3_3") (pintype "passive"))
      (node (ref "P4") (pin "1") (pinfunction "1_1") (pintype "passive"))
      (node (ref "P5") (pin "1") (pinfunction "1_1") (pintype "passive"))
      (node (ref "P6") (pin "1") (pinfunction "1_1") (pintype "passive"))
      (node (ref "P7") (pin "1") (pinfunction "1_1") (pintype "passive"))
      (node (ref "P8") (pin "1") (pinfunction "1_1") (pintype "passive"))
      (node (ref "P9") (pin "1") (pinfunction "1_1") (pintype "passive"))
    )
    (net (code "73") (name "Net-(J2-Pad1)") (class "Default")
      (node (ref "J2") (pin "1") (pintype "input"))
      (node (ref "P23") (pin "2") (pinfunction "2_2") (pintype "passive"))
    )
    (net (code "74") (name "Net-(J2-Pad3)") (class "Default")
      (node (ref "J2") (pin "3") (pintype "input"))
      (node (ref "P23") (pin "6") (pinfunction "6_6") (pintype "passive"))
    )
    (net (code "75") (name "Net-(J2-Pad4)") (class "Default")
      (node (ref "J2") (pin "4") (pintype "input"))
      (node (ref "P23") (pin "8") (pinfunction "8_8") (pintype "passive"))
    )
    (net (code "76") (name "Net-(J3-Pad2)") (class "Default")
      (node (ref "J3") (pin "2") (pintype "input"))
      (node (ref "P27") (pin "8") (pinfunction "8_8") (pintype "passive"))
    )
    (net (code "77") (name "Net-(J3-Pad3)") (class "Default")
      (node (ref "J3") (pin "3") (pintype "input"))
      (node (ref "P27") (pin "6") (pinfunction "6_6") (pintype "passive"))
    )
    (net (code "78") (name "Net-(J3-Pad5)") (class "Default")
      (node (ref "J3") (pin "5") (pintype "input"))
      (node (ref "P27") (pin "2") (pinfunction "2_2") (pintype "passive"))
    )
    (net (code "79") (name "VCC") (class "Default")
      (node (ref "*1") (pin "2") (pinfunction "2_2") (pintype "passive"))
      (node (ref "*11") (pin "2") (pinfunction "2_2") (pintype "passive"))
      (node (ref "*13") (pin "2") (pinfunction "2_2") (pintype "passive"))
      (node (ref "*15") (pin "2") (pinfunction "2_2") (pintype "passive"))
      (node (ref "*17") (pin "2") (pinfunction "2_2") (pintype "passive"))
      (node (ref "*19") (pin "2") (pinfunction "2_2") (pintype "passive"))
      (node (ref "*25") (pin "2") (pinfunction "2_2") (pintype "passive"))
      (node (ref "*26") (pin "2") (pinfunction "2_2") (pintype "passive"))
      (node (ref "*27") (pin "2") (pinfunction "2_2") (pintype "passive"))
      (node (ref "*28") (pin "2") (pinfunction "2_2") (pintype "passive"))
      (node (ref "*3") (pin "2") (pinfunction "2_2") (pintype "passive"))
      (node (ref "*5") (pin "2") (pinfunction "2_2") (pintype "passive"))
      (node (ref "*7") (pin "2") (pinfunction "2_2") (pintype "passive"))
      (node (ref "*9") (pin "2") (pinfunction "2_2") (pintype "passive"))
      (node (ref "P10") (pin "2") (pinfunction "2_2") (pintype "passive"))
      (node (ref "P12") (pin "2") (pinfunction "2_2") (pintype "passive"))
      (node (ref "P14") (pin "2") (pinfunction "2_2") (pintype "passive"))
      (node (ref "P16") (pin "2") (pinfunction "2_2") (pintype "passive"))
      (node (ref "P18") (pin "2") (pinfunction "2_2") (pintype "passive"))
      (node (ref "P20") (pin "2") (pinfunction "2_2") (pintype "passive"))
      (node (ref "P22") (pin "2") (pinfunction "2_2") (pintype "passive"))
      (node (ref "P25") (pin "2") (pinfunction "2_2") (pintype "passive"))
      (node (ref "P26") (pin "2") (pinfunction "2_2") (pintype "passive"))
      (node (ref "P33") (pin "2") (pinfunction "2_2") (pintype "passive"))
      (node (ref "P34") (pin "2") (pinfunction "2_2") (pintype "passive"))
      (node (ref "P35") (pin "2") (pinfunction "2_2") (pintype "passive"))
      (node (ref "P36") (pin "2") (pinfunction "2_2") (pintype "passive"))
      (node (ref "P8") (pin "2") (pinfunction "2_2") (pintype "passive"))
    )
    (net (code "80") (name "unconnected-(J2-Pad2)") (class "Default")
      (node (ref "J2") (pin "2") (pintype "input"))
    )
    (net (code "81") (name "unconnected-(J2-Pad5)") (class "Default")
      (node (ref "J2") (pin "5") (pintype "input"))
    )
    (net (code "82") (name "unconnected-(J2-Pad6)") (class "Default")
      (node (ref "J2") (pin "6") (pintype "input"))
    )
    (net (code "83") (name "unconnected-(J2-Pad7)") (class "Default")
      (node (ref "J2") (pin "7") (pintype "input"))
    )
    (net (code "84") (name "unconnected-(J2-Pad8)") (class "Default")
      (node (ref "J2") (pin "8") (pintype "input"))
    )
    (net (code "85") (name "unconnected-(J2-Pad9)") (class "Default")
      (node (ref "J2") (pin "9") (pintype "input"))
    )
    (net (code "86") (name "unconnected-(J3-Pad1)") (class "Default")
      (node (ref "J3") (pin "1") (pintype "input"))
    )
    (net (code "87") (name "unconnected-(J3-Pad4)") (class "Default")
      (node (ref "J3") (pin "4") (pintype "input"))
    )
    (net (code "88") (name "unconnected-(J3-Pad6)") (class "Default")
      (node (ref "J3") (pin "6") (pintype "input"))
    )
    (net (code "89") (name "unconnected-(J3-Pad7)") (class "Default")
      (node (ref "J3") (pin "7") (pintype "input"))
    )
    (net (code "90") (name "unconnected-(J3-Pad8)") (class "Default")
      (node (ref "J3") (pin "8") (pintype "input"))
    )
    (net (code "91") (name "unconnected-(J3-Pad9)") (class "Default")
      (node (ref "J3") (pin "9") (pintype "input"))
    )
    (net (code "92") (name "unconnected-(P23-Pad3)") (class "Default")
      (node (ref "P23") (pin "3") (pinfunction "3_3") (pintype "passive"))
    )
    (net (code "93") (name "unconnected-(P23-Pad9)") (class "Default")
      (node (ref "P23") (pin "9") (pinfunction "9_9") (pintype "passive"))
    )
    (net (code "94") (name "unconnected-(P27-Pad3)") (class "Default")
      (node (ref "P27") (pin "3") (pinfunction "3_3") (pintype "passive"))
    )
    (net (code "95") (name "unconnected-(P27-Pad9)") (class "Default")
      (node (ref "P27") (pin "9") (pinfunction "9_9") (pintype "passive"))
    )
  )
)
